# placa.net
KiCad netlist of a schematic drawn in EAGLE
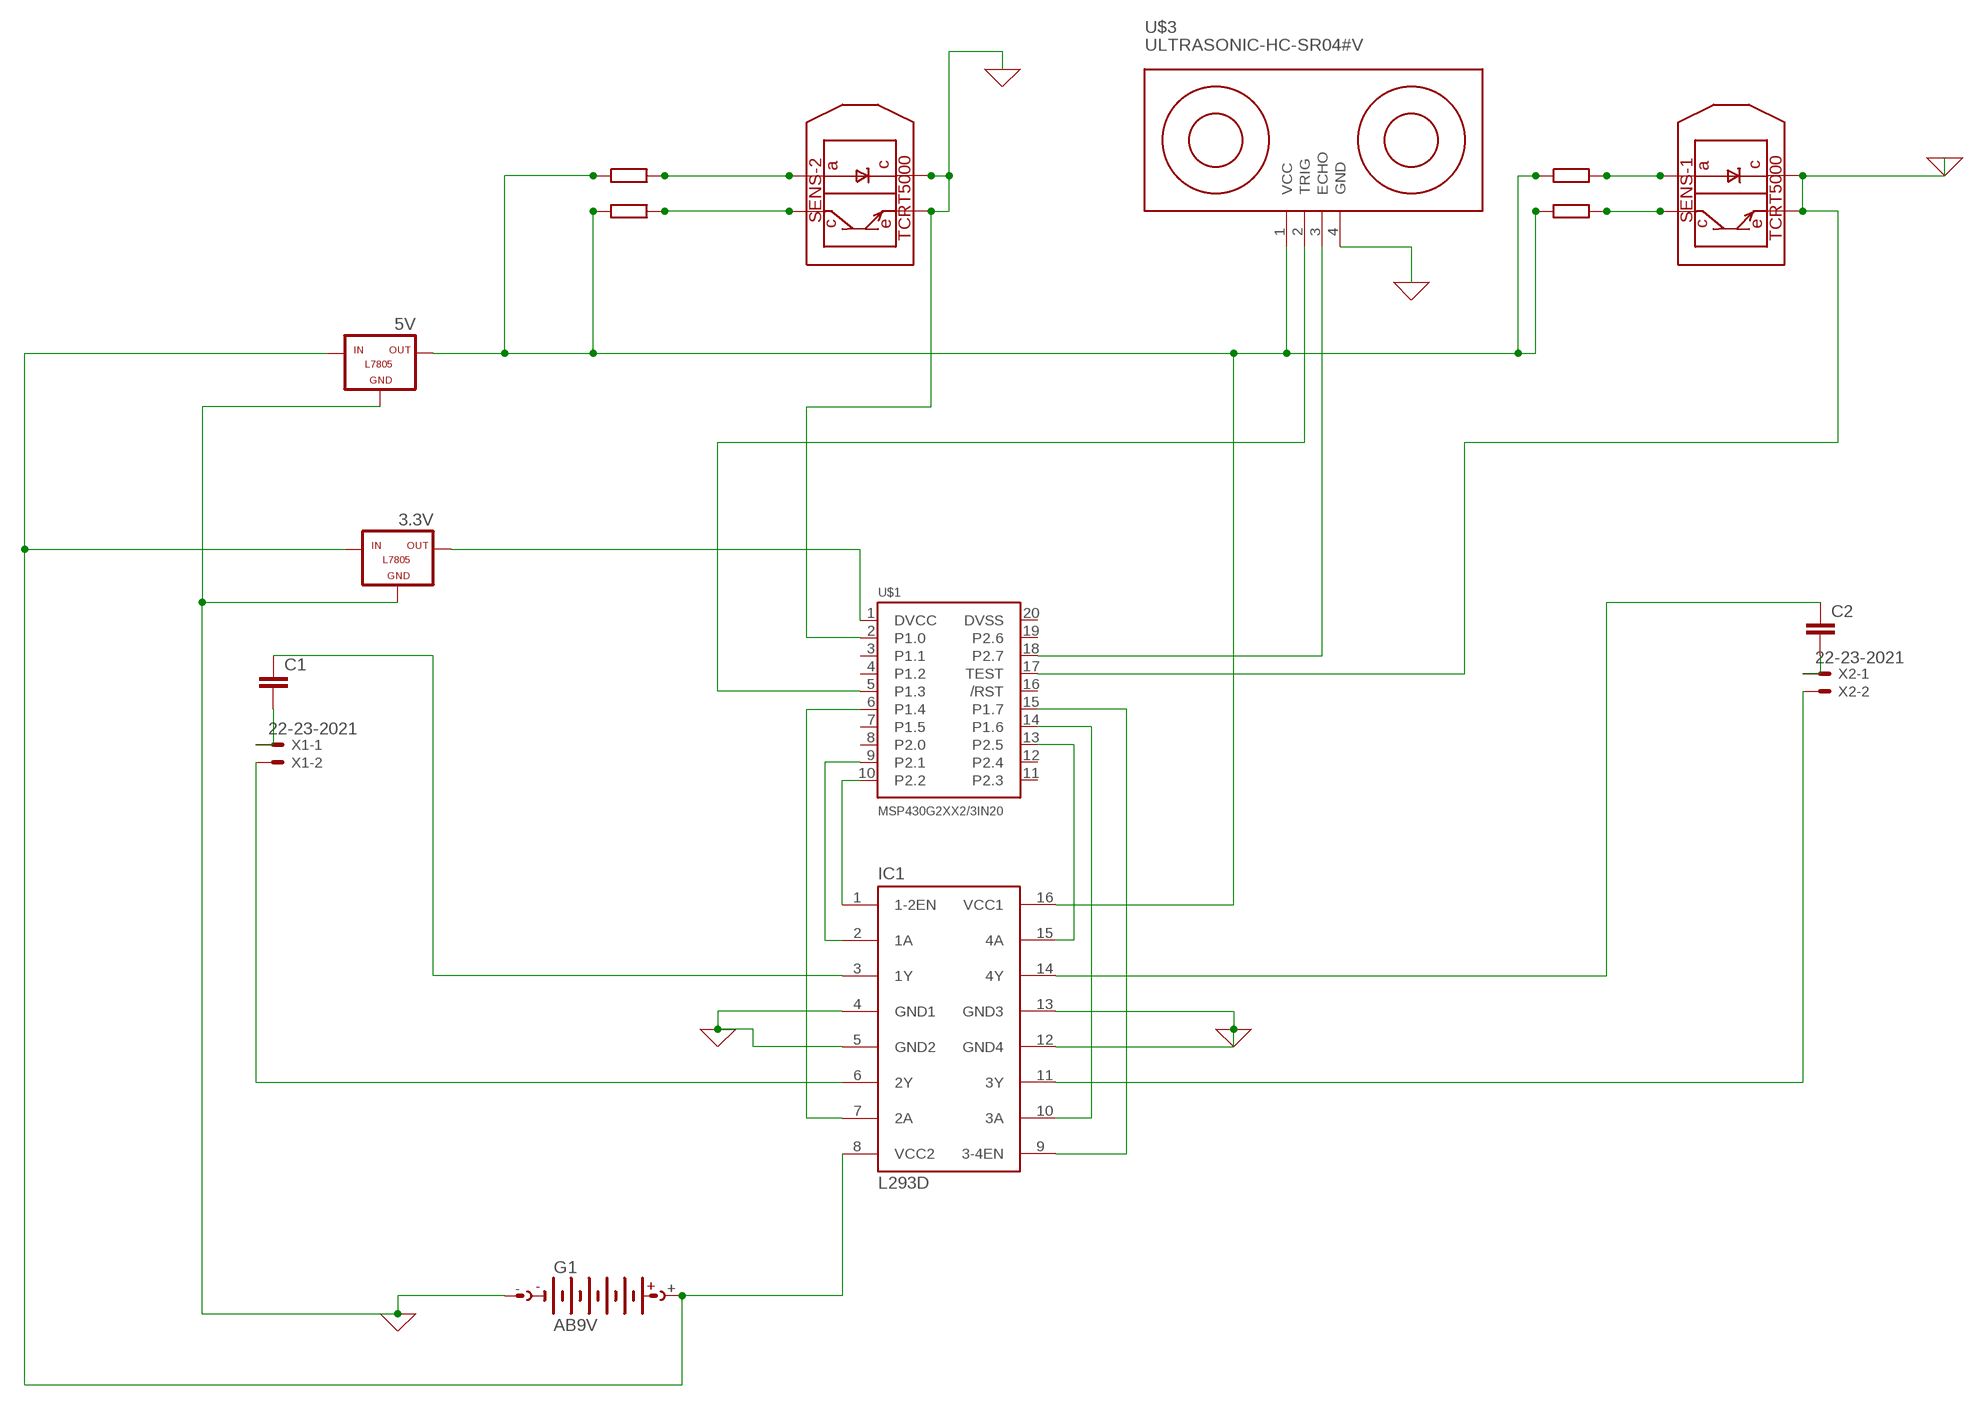
[diagram p0: schematic, sheet 1]

(export (version "E")
  (design (tool "Eeschema 10.0.6"))
  (components
    (comp (ref "3.3V")
      (value "-L7805")
      (footprint "eagle-import:L7805")
      (libsource (lib "eagle-import") (part "-L7805"))
    )
    (comp (ref "5V")
      (value "-L7805")
      (footprint "eagle-import:L7805")
      (libsource (lib "eagle-import") (part "-L7805"))
    )
    (comp (ref "C1")
      (value "C2.5/2")
      (footprint "eagle-import:C2.5-2")
      (libsource (lib "eagle-import") (part "C2.5/2"))
    )
    (comp (ref "C2")
      (value "C2.5/2")
      (footprint "eagle-import:C2.5-2")
      (libsource (lib "eagle-import") (part "C2.5/2"))
    )
    (comp (ref "G1")
      (value "AB9V")
      (footprint "eagle-import:AB9V")
      (libsource (lib "eagle-import") (part "AB9V"))
    )
    (comp (ref "IC1")
      (value "L293D")
      (footprint "eagle-import:DIL16")
      (libsource (lib "eagle-import") (part "L293D"))
    )
    (comp (ref "SENS-1")
      (value "TCRT5000")
      (footprint "eagle-import:5000")
      (libsource (lib "eagle-import") (part "TCRT5000"))
    )
    (comp (ref "SENS-2")
      (value "TCRT5000")
      (footprint "eagle-import:5000")
      (libsource (lib "eagle-import") (part "TCRT5000"))
    )
    (comp (ref "U$1")
      (value "MSP430G2XX2/3IN20")
      (footprint "eagle-import:DIL20")
      (libsource (lib "eagle-import") (part "MSP430G2XX2/3IN20"))
    )
    (comp (ref "U$3")
      (value "ULTRASONIC-HC-SR04#V")
      (footprint "eagle-import:ULTRASONIC-HC-SR04#V")
      (libsource (lib "eagle-import") (part "ULTRASONIC-HC-SR04#V"))
    )
    (comp (ref "X1")
      (value "22-23-2021")
      (footprint "eagle-import:22-23-2021")
      (fields (field (name "MF") "MOLEX"))
      (libsource (lib "eagle-import") (part "22-23-2021"))
    )
    (comp (ref "X2")
      (value "22-23-2021")
      (footprint "eagle-import:22-23-2021")
      (fields (field (name "MF") "MOLEX"))
      (libsource (lib "eagle-import") (part "22-23-2021"))
    )
  )
  (nets
    (net (code "1") (name "/DVSS") (class "Default")
      (node (ref "U$1") (pin "20") (pinfunction "DVSS_20") (pintype "power_in"))
    )
    (net (code "2") (name "GND") (class "Default")
      (node (ref "3.3V") (pin "GND") (pinfunction "GND_GND") (pintype "input"))
      (node (ref "5V") (pin "GND") (pinfunction "GND_GND") (pintype "input"))
      (node (ref "G1") (pin "-") (pinfunction "-_-") (pintype "passive"))
      (node (ref "IC1") (pin "12") (pinfunction "GND4_12") (pintype "power_in"))
      (node (ref "IC1") (pin "13") (pinfunction "GND3_13") (pintype "power_in"))
      (node (ref "IC1") (pin "4") (pinfunction "GND1_4") (pintype "power_in"))
      (node (ref "IC1") (pin "5") (pinfunction "GND2_5") (pintype "power_in"))
      (node (ref "SENS-1") (pin "P$2") (pinfunction "P$2_P$2") (pintype "passive"))
      (node (ref "SENS-1") (pin "P$4") (pinfunction "P$4_P$4") (pintype "passive"))
      (node (ref "SENS-2") (pin "P$2") (pinfunction "P$2_P$2") (pintype "passive"))
      (node (ref "SENS-2") (pin "P$4") (pinfunction "P$4_P$4") (pintype "passive"))
      (node (ref "U$1") (pin "17") (pinfunction "TEST_17") (pintype "bidirectional"))
      (node (ref "U$1") (pin "2") (pinfunction "P1.0_2") (pintype "bidirectional"))
      (node (ref "U$3") (pin "4") (pinfunction "GND_4") (pintype "power_in"))
    )
    (net (code "3") (name "Net-(IC1-1-2EN)") (class "Default")
      (node (ref "IC1") (pin "1") (pinfunction "1-2EN_1") (pintype "input"))
      (node (ref "U$1") (pin "10") (pinfunction "P2.2_10") (pintype "bidirectional"))
    )
    (net (code "4") (name "Net-(IC1-1A)") (class "Default")
      (node (ref "IC1") (pin "2") (pinfunction "1A_2") (pintype "input"))
      (node (ref "U$1") (pin "9") (pinfunction "P2.1_9") (pintype "bidirectional"))
    )
    (net (code "5") (name "Net-(IC1-1Y)") (class "Default")
      (node (ref "C1") (pin "1") (pinfunction "1_1") (pintype "passive"))
      (node (ref "IC1") (pin "3") (pinfunction "1Y_3") (pintype "output"))
    )
    (net (code "6") (name "Net-(IC1-2A)") (class "Default")
      (node (ref "IC1") (pin "7") (pinfunction "2A_7") (pintype "input"))
      (node (ref "U$1") (pin "6") (pinfunction "P1.4_6") (pintype "bidirectional"))
    )
    (net (code "7") (name "Net-(IC1-2Y)") (class "Default")
      (node (ref "IC1") (pin "6") (pinfunction "2Y_6") (pintype "output"))
      (node (ref "X1") (pin "2") (pinfunction "S_2") (pintype "passive"))
    )
    (net (code "8") (name "Net-(IC1-3-4EN)") (class "Default")
      (node (ref "IC1") (pin "9") (pinfunction "3-4EN_9") (pintype "input"))
      (node (ref "U$1") (pin "15") (pinfunction "P1.7_15") (pintype "bidirectional"))
    )
    (net (code "9") (name "Net-(IC1-3A)") (class "Default")
      (node (ref "IC1") (pin "10") (pinfunction "3A_10") (pintype "input"))
      (node (ref "U$1") (pin "14") (pinfunction "P1.6_14") (pintype "bidirectional"))
    )
    (net (code "10") (name "Net-(IC1-3Y)") (class "Default")
      (node (ref "IC1") (pin "11") (pinfunction "3Y_11") (pintype "output"))
      (node (ref "X2") (pin "2") (pinfunction "S_2") (pintype "passive"))
    )
    (net (code "11") (name "Net-(IC1-4A)") (class "Default")
      (node (ref "IC1") (pin "15") (pinfunction "4A_15") (pintype "input"))
      (node (ref "U$1") (pin "13") (pinfunction "P2.5_13") (pintype "bidirectional"))
    )
    (net (code "12") (name "Net-(IC1-4Y)") (class "Default")
      (node (ref "C2") (pin "1") (pinfunction "1_1") (pintype "passive"))
      (node (ref "IC1") (pin "14") (pinfunction "4Y_14") (pintype "output"))
    )
    (net (code "13") (name "Net-(IC1-VCC1)") (class "Default")
      (node (ref "5V") (pin "OUT") (pinfunction "OUT_OUT") (pintype "passive"))
      (node (ref "IC1") (pin "16") (pinfunction "VCC1_16") (pintype "power_in"))
      (node (ref "U$3") (pin "1") (pinfunction "VCC_1") (pintype "power_in"))
    )
    (net (code "14") (name "Net-(IC1-VCC2)") (class "Default")
      (node (ref "3.3V") (pin "IN") (pinfunction "IN_IN") (pintype "input"))
      (node (ref "5V") (pin "IN") (pinfunction "IN_IN") (pintype "input"))
      (node (ref "G1") (pin "+") (pinfunction "+_+") (pintype "passive"))
      (node (ref "IC1") (pin "8") (pinfunction "VCC2_8") (pintype "power_in"))
    )
    (net (code "15") (name "Net-(U$1-DVCC)") (class "Default")
      (node (ref "3.3V") (pin "OUT") (pinfunction "OUT_OUT") (pintype "passive"))
      (node (ref "U$1") (pin "1") (pinfunction "DVCC_1") (pintype "power_in"))
    )
    (net (code "16") (name "Net-(U$1-P1.3)") (class "Default")
      (node (ref "U$1") (pin "5") (pinfunction "P1.3_5") (pintype "bidirectional"))
      (node (ref "U$3") (pin "2") (pinfunction "TRIG_2") (pintype "input"))
    )
    (net (code "17") (name "Net-(U$1-P2.7)") (class "Default")
      (node (ref "U$1") (pin "18") (pinfunction "P2.7_18") (pintype "bidirectional"))
      (node (ref "U$3") (pin "3") (pinfunction "ECHO_3") (pintype "output"))
    )
    (net (code "18") (name "Net-(X1A-S)") (class "Default")
      (node (ref "C1") (pin "2") (pinfunction "2_2") (pintype "passive"))
      (node (ref "X1") (pin "1") (pinfunction "S_1") (pintype "passive"))
    )
    (net (code "19") (name "Net-(X2A-S)") (class "Default")
      (node (ref "C2") (pin "2") (pinfunction "2_2") (pintype "passive"))
      (node (ref "X2") (pin "1") (pinfunction "S_1") (pintype "passive"))
    )
    (net (code "20") (name "unconnected-(SENS-1-PadP$1)") (class "Default")
      (node (ref "SENS-1") (pin "P$1") (pinfunction "P$1_P$1") (pintype "passive"))
    )
    (net (code "21") (name "unconnected-(SENS-1-PadP$3)") (class "Default")
      (node (ref "SENS-1") (pin "P$3") (pinfunction "P$3_P$3") (pintype "passive"))
    )
    (net (code "22") (name "unconnected-(SENS-2-PadP$1)") (class "Default")
      (node (ref "SENS-2") (pin "P$1") (pinfunction "P$1_P$1") (pintype "passive"))
    )
    (net (code "23") (name "unconnected-(SENS-2-PadP$3)") (class "Default")
      (node (ref "SENS-2") (pin "P$3") (pinfunction "P$3_P$3") (pintype "passive"))
    )
    (net (code "24") (name "unconnected-(U$1-P1.1-Pad3)") (class "Default")
      (node (ref "U$1") (pin "3") (pinfunction "P1.1_3") (pintype "bidirectional"))
    )
    (net (code "25") (name "unconnected-(U$1-P1.2-Pad4)") (class "Default")
      (node (ref "U$1") (pin "4") (pinfunction "P1.2_4") (pintype "bidirectional"))
    )
    (net (code "26") (name "unconnected-(U$1-P1.5-Pad7)") (class "Default")
      (node (ref "U$1") (pin "7") (pinfunction "P1.5_7") (pintype "bidirectional"))
    )
    (net (code "27") (name "unconnected-(U$1-P2.0-Pad8)") (class "Default")
      (node (ref "U$1") (pin "8") (pinfunction "P2.0_8") (pintype "bidirectional"))
    )
    (net (code "28") (name "unconnected-(U$1-P2.3-Pad11)") (class "Default")
      (node (ref "U$1") (pin "11") (pinfunction "P2.3_11") (pintype "bidirectional"))
    )
    (net (code "29") (name "unconnected-(U$1-P2.4-Pad12)") (class "Default")
      (node (ref "U$1") (pin "12") (pinfunction "P2.4_12") (pintype "bidirectional"))
    )
    (net (code "30") (name "unconnected-(U$1-P2.6-Pad19)") (class "Default")
      (node (ref "U$1") (pin "19") (pinfunction "P2.6_19") (pintype "bidirectional"))
    )
    (net (code "31") (name "unconnected-(U$1-{slash}RST-Pad16)") (class "Default")
      (node (ref "U$1") (pin "16") (pinfunction "/RST_16") (pintype "bidirectional"))
    )
  )
)
